# accelerometer.net
KiCad netlist of a schematic drawn in Altium Designer
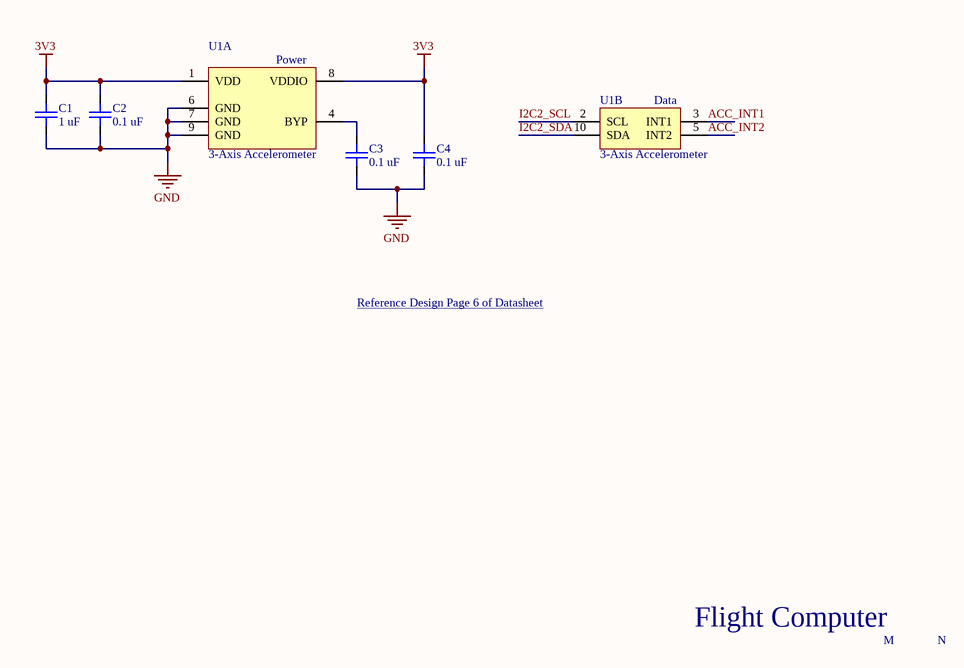
[diagram p0: accelerometer.SchDoc]

(export (version "E")
  (design (tool "Eeschema 10.0.6"))
  (components
    (comp (ref "C1")
      (value "1 uF")
      (footprint "CAP-CER-0805-TALL")
      (description "10%, 0805")
      (libsource (lib "passive") (part "CAP-CER-1uF-10V"))
    )
    (comp (ref "C2")
      (value "0.1 uF")
      (footprint "CAP-CER-0805-SHORT")
      (description "10%, 0805")
      (libsource (lib "passive") (part "CAP-CER-0.1uF-25V"))
    )
    (comp (ref "C3")
      (value "0.1 uF")
      (footprint "CAP-CER-0805-SHORT")
      (description "10%, 0805")
      (libsource (lib "passive") (part "CAP-CER-0.1uF-25V"))
    )
    (comp (ref "C4")
      (value "0.1 uF")
      (footprint "CAP-CER-0805-SHORT")
      (description "10%, 0805")
      (libsource (lib "passive") (part "CAP-CER-0.1uF-25V"))
    )
    (comp (ref "U1")
      (value "3-Axis Accelerometer")
      (footprint "SON10")
      (description "3-Axis, 12-bit Digital Accelerometer, I2C 400kHz")
      (libsource (lib "ic") (part "MMA8652FC"))
    )
  )
  (nets
    (net (code "1") (name "/ACC_INT1") (class "Default")
      (node (ref "U1") (pin "3") (pinfunction "INT1_3") (pintype "passive"))
    )
    (net (code "2") (name "/ACC_INT2") (class "Default")
      (node (ref "U1") (pin "5") (pinfunction "INT2_5") (pintype "passive"))
    )
    (net (code "3") (name "/I2C2_SCL") (class "Default")
      (node (ref "U1") (pin "2") (pinfunction "SCL_2") (pintype "passive"))
    )
    (net (code "4") (name "/I2C2_SDA") (class "Default")
      (node (ref "U1") (pin "10") (pinfunction "SDA_10") (pintype "passive"))
    )
    (net (code "5") (name "3V3") (class "Default")
      (node (ref "C1") (pin "2") (pinfunction "2_2") (pintype "passive"))
      (node (ref "C2") (pin "2") (pinfunction "2_2") (pintype "passive"))
      (node (ref "C4") (pin "2") (pinfunction "2_2") (pintype "passive"))
      (node (ref "U1") (pin "1") (pinfunction "VDD_1") (pintype "passive"))
      (node (ref "U1") (pin "8") (pinfunction "VDDIO_8") (pintype "passive"))
    )
    (net (code "6") (name "GND") (class "Default")
      (node (ref "C1") (pin "1") (pinfunction "1_1") (pintype "passive"))
      (node (ref "C2") (pin "1") (pinfunction "1_1") (pintype "passive"))
      (node (ref "C3") (pin "1") (pinfunction "1_1") (pintype "passive"))
      (node (ref "C4") (pin "1") (pinfunction "1_1") (pintype "passive"))
      (node (ref "U1") (pin "6") (pinfunction "GND_6") (pintype "passive"))
      (node (ref "U1") (pin "7") (pinfunction "GND_7") (pintype "passive"))
      (node (ref "U1") (pin "9") (pinfunction "GND_9") (pintype "passive"))
    )
    (net (code "7") (name "Net-(U1A-BYP)") (class "Default")
      (node (ref "C3") (pin "2") (pinfunction "2_2") (pintype "passive"))
      (node (ref "U1") (pin "4") (pinfunction "BYP_4") (pintype "passive"))
    )
  )
)
